# HyperPower.net
KiCad netlist of a schematic drawn in EAGLE
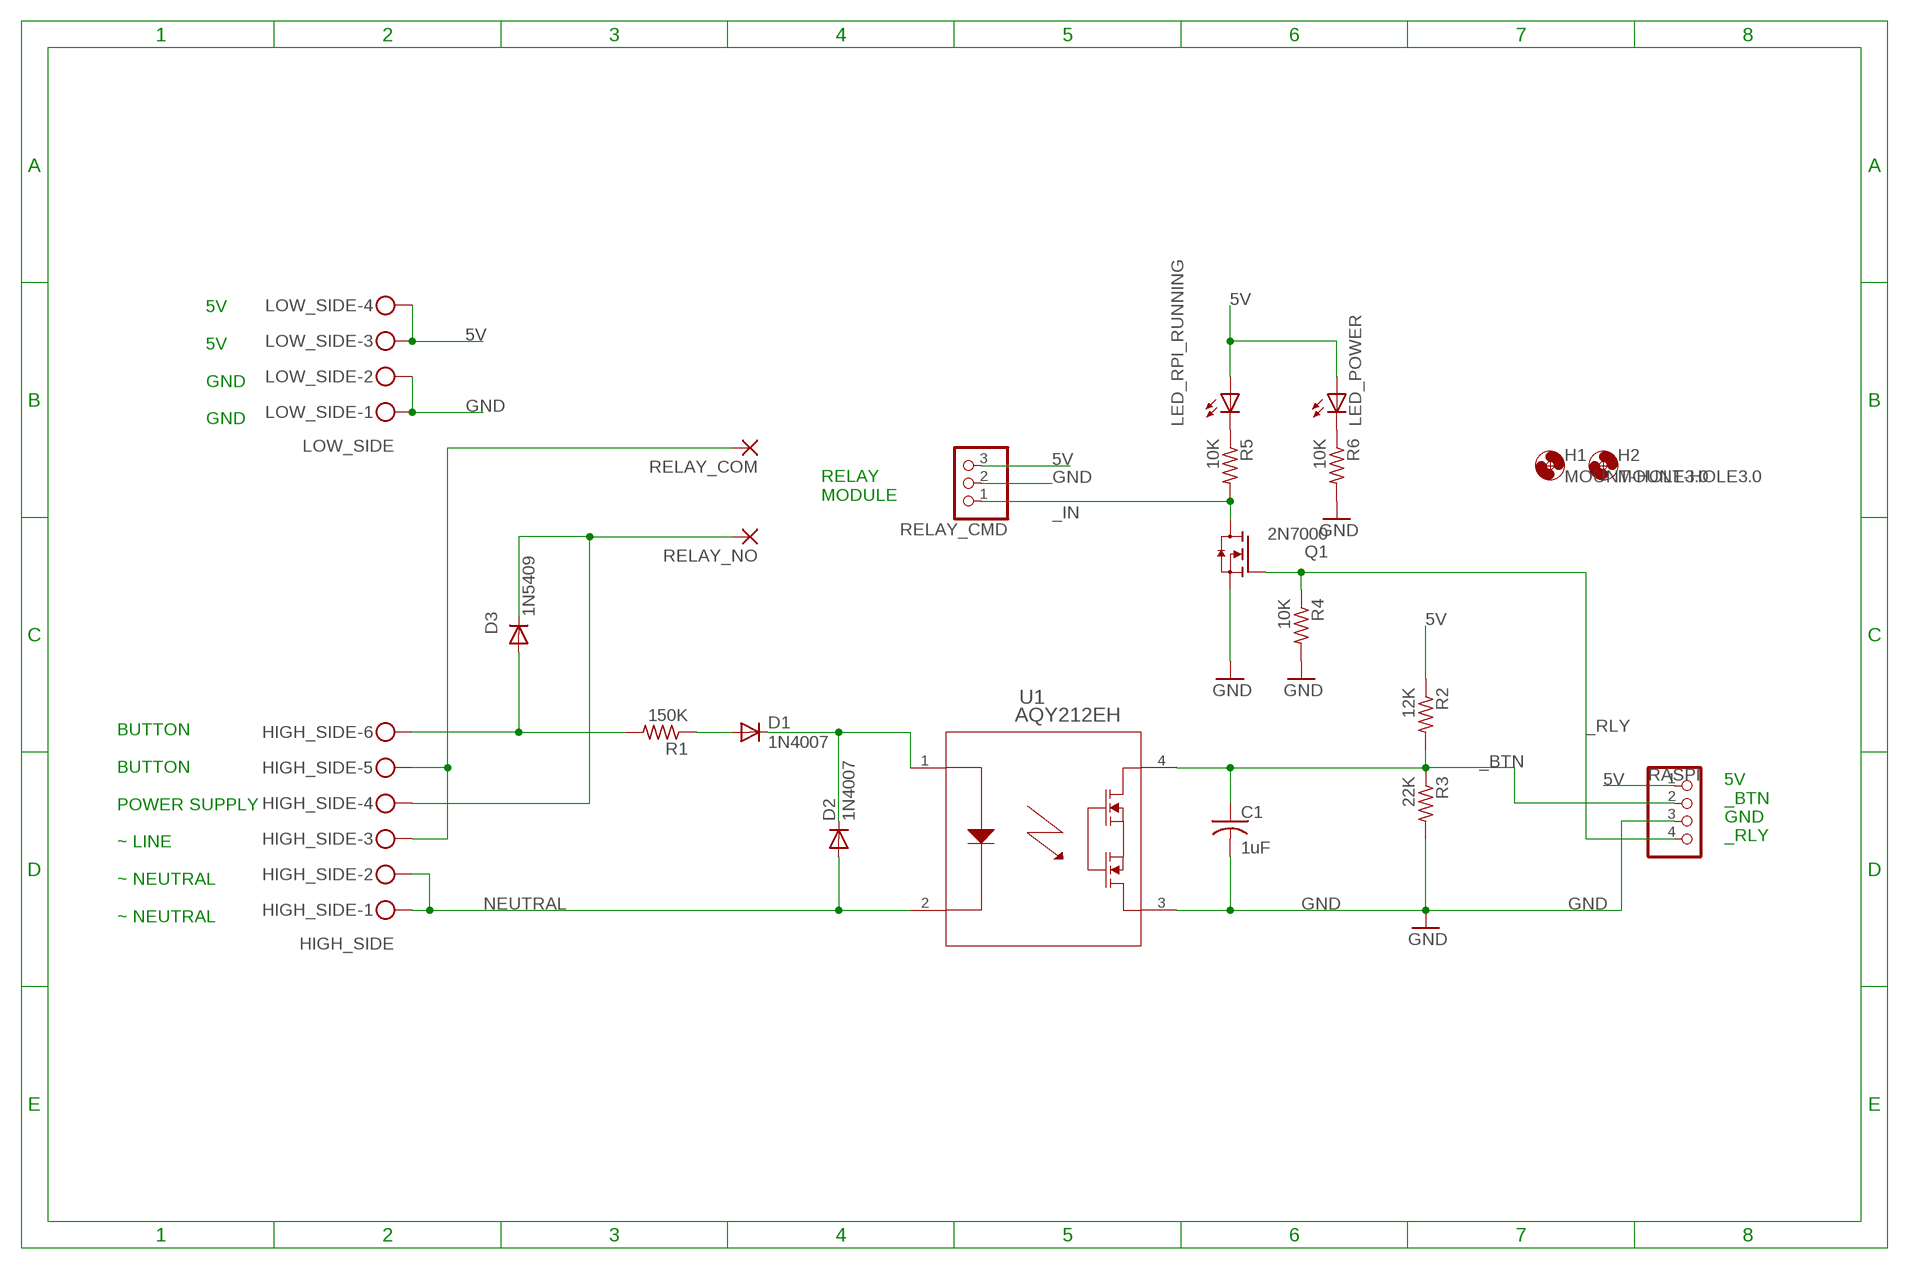
[diagram p0: schematic, sheet 1]

(export (version "E")
  (design (tool "Eeschema 10.0.6"))
  (components
    (comp (ref "C1")
      (value "1uF")
      (footprint "eagle-import:C025-040X050")
      (libsource (lib "eagle-import") (part "C-US025-040X050"))
    )
    (comp (ref "D1")
      (value "1N4007")
      (footprint "eagle-import:DO41-10")
      (libsource (lib "eagle-import") (part "1N4004"))
    )
    (comp (ref "D2")
      (value "1N4007")
      (footprint "eagle-import:DO41-10")
      (libsource (lib "eagle-import") (part "1N4004"))
    )
    (comp (ref "D3")
      (value "1N5409")
      (footprint "eagle-import:DO201-15")
      (libsource (lib "eagle-import") (part "1N5400"))
    )
    (comp (ref "H1")
      (value "MOUNT-HOLE3.0")
      (footprint "eagle-import:3,0")
      (libsource (lib "eagle-import") (part "MOUNT-HOLE3.0"))
    )
    (comp (ref "H2")
      (value "MOUNT-HOLE3.0")
      (footprint "eagle-import:3,0")
      (libsource (lib "eagle-import") (part "MOUNT-HOLE3.0"))
    )
    (comp (ref "HIGH_SIDE")
      (value "HIGH_SIDE")
      (footprint "eagle-import:MKDSN1,5_6-5,08")
      (libsource (lib "eagle-import") (part "MKDSN1,5/6-5,08"))
    )
    (comp (ref "LED_POWER")
      (value "LED_ELD260")
      (footprint "eagle-import:LED_LD260")
      (libsource (lib "eagle-import") (part "LED_ELD260"))
    )
    (comp (ref "LED_RPI_RUNNING")
      (value "LED_ELD260")
      (footprint "eagle-import:LED_LD260")
      (libsource (lib "eagle-import") (part "LED_ELD260"))
    )
    (comp (ref "LOW_SIDE")
      (value "LOW_SIDE")
      (footprint "eagle-import:MKDSN1,5_4-5,08")
      (libsource (lib "eagle-import") (part "MKDSN1,5/4-5,08"))
    )
    (comp (ref "Q1")
      (value "2N7000")
      (footprint "eagle-import:TO92")
      (fields (field (name "MF") "STMicroelectronics"))
      (libsource (lib "eagle-import") (part "2N7000"))
    )
    (comp (ref "R1")
      (value "150K")
      (footprint "eagle-import:0207_10")
      (libsource (lib "eagle-import") (part "R-US_0207/10"))
    )
    (comp (ref "R2")
      (value "12K")
      (footprint "eagle-import:0207_10")
      (libsource (lib "eagle-import") (part "R-US_0207/10"))
    )
    (comp (ref "R3")
      (value "22K")
      (footprint "eagle-import:0207_10")
      (libsource (lib "eagle-import") (part "R-US_0207/10"))
    )
    (comp (ref "R4")
      (value "10K")
      (footprint "eagle-import:0207_10")
      (libsource (lib "eagle-import") (part "R-US_0207/10"))
    )
    (comp (ref "R5")
      (value "10K")
      (footprint "eagle-import:0207_10")
      (libsource (lib "eagle-import") (part "R-US_0207/10"))
    )
    (comp (ref "R6")
      (value "10K")
      (footprint "eagle-import:0207_10")
      (libsource (lib "eagle-import") (part "R-US_0207/10"))
    )
    (comp (ref "RASPI")
      (value "PINHD-1X4")
      (footprint "eagle-import:1X04")
      (libsource (lib "eagle-import") (part "PINHD-1X4"))
    )
    (comp (ref "RELAY_CMD")
      (value "PINHD-1X3")
      (footprint "eagle-import:1X03")
      (libsource (lib "eagle-import") (part "PINHD-1X3"))
    )
    (comp (ref "RELAY_COM")
      (value "3,81/1,4")
      (footprint "eagle-import:3,81_1,4")
      (libsource (lib "eagle-import") (part "3,81/1,4"))
    )
    (comp (ref "RELAY_NO")
      (value "3,81/1,4")
      (footprint "eagle-import:3,81_1,4")
      (libsource (lib "eagle-import") (part "3,81/1,4"))
    )
    (comp (ref "U1")
      (value "AQY212EH")
      (footprint "eagle-import:PAN_AQY21-DIP4_PAN")
      (libsource (lib "eagle-import") (part "AQY212EH"))
    )
  )
  (nets
    (net (code "1") (name "/5V") (class "Default")
      (node (ref "LED_POWER") (pin "A") (pinfunction "A_A") (pintype "passive"))
      (node (ref "LED_RPI_RUNNING") (pin "A") (pinfunction "A_A") (pintype "passive"))
      (node (ref "LOW_SIDE") (pin "3") (pinfunction "KL_3") (pintype "passive"))
      (node (ref "LOW_SIDE") (pin "4") (pinfunction "KL_4") (pintype "passive"))
      (node (ref "R2") (pin "1") (pinfunction "1_1") (pintype "passive"))
      (node (ref "RASPI") (pin "1") (pinfunction "1_1") (pintype "passive"))
      (node (ref "RELAY_CMD") (pin "3") (pinfunction "3_3") (pintype "passive"))
    )
    (net (code "2") (name "/NEUTRAL") (class "Default")
      (node (ref "D2") (pin "A") (pinfunction "A_A") (pintype "passive"))
      (node (ref "HIGH_SIDE") (pin "1") (pinfunction "KL_1") (pintype "passive"))
      (node (ref "HIGH_SIDE") (pin "2") (pinfunction "KL_2") (pintype "passive"))
      (node (ref "U1") (pin "2") (pinfunction "2_2") (pintype "passive"))
    )
    (net (code "3") (name "/_BTN") (class "Default")
      (node (ref "C1") (pin "1") (pinfunction "1_1") (pintype "passive"))
      (node (ref "R2") (pin "2") (pinfunction "2_2") (pintype "passive"))
      (node (ref "R3") (pin "1") (pinfunction "1_1") (pintype "passive"))
      (node (ref "RASPI") (pin "2") (pinfunction "2_2") (pintype "passive"))
      (node (ref "U1") (pin "4") (pinfunction "4_4") (pintype "passive"))
    )
    (net (code "4") (name "/_IN") (class "Default")
      (node (ref "Q1") (pin "3") (pinfunction "D_3") (pintype "passive"))
      (node (ref "R5") (pin "2") (pinfunction "2_2") (pintype "passive"))
      (node (ref "RELAY_CMD") (pin "1") (pinfunction "1_1") (pintype "passive"))
    )
    (net (code "5") (name "/_RLY") (class "Default")
      (node (ref "Q1") (pin "2") (pinfunction "G_2") (pintype "passive"))
      (node (ref "R4") (pin "1") (pinfunction "1_1") (pintype "passive"))
      (node (ref "RASPI") (pin "4") (pinfunction "4_4") (pintype "passive"))
    )
    (net (code "6") (name "GND") (class "Default")
      (node (ref "C1") (pin "2") (pinfunction "2_2") (pintype "passive"))
      (node (ref "LOW_SIDE") (pin "1") (pinfunction "KL_1") (pintype "passive"))
      (node (ref "LOW_SIDE") (pin "2") (pinfunction "KL_2") (pintype "passive"))
      (node (ref "Q1") (pin "1") (pinfunction "S_1") (pintype "passive"))
      (node (ref "R3") (pin "2") (pinfunction "2_2") (pintype "passive"))
      (node (ref "R4") (pin "2") (pinfunction "2_2") (pintype "passive"))
      (node (ref "R6") (pin "2") (pinfunction "2_2") (pintype "passive"))
      (node (ref "RASPI") (pin "3") (pinfunction "3_3") (pintype "passive"))
      (node (ref "RELAY_CMD") (pin "2") (pinfunction "2_2") (pintype "passive"))
      (node (ref "U1") (pin "3") (pinfunction "3_3") (pintype "passive"))
    )
    (net (code "7") (name "Net-(D1-PadA)") (class "Default")
      (node (ref "D1") (pin "A") (pinfunction "A_A") (pintype "passive"))
      (node (ref "R1") (pin "1") (pinfunction "1_1") (pintype "passive"))
    )
    (net (code "8") (name "Net-(D1-PadC)") (class "Default")
      (node (ref "D1") (pin "C") (pinfunction "C_C") (pintype "passive"))
      (node (ref "D2") (pin "C") (pinfunction "C_C") (pintype "passive"))
      (node (ref "U1") (pin "1") (pinfunction "1_1") (pintype "passive"))
    )
    (net (code "9") (name "Net-(HIGH_SIDEC-KL)") (class "Default")
      (node (ref "HIGH_SIDE") (pin "3") (pinfunction "KL_3") (pintype "passive"))
      (node (ref "HIGH_SIDE") (pin "5") (pinfunction "KL_5") (pintype "passive"))
      (node (ref "RELAY_COM") (pin "1") (pinfunction "P_1") (pintype "passive"))
    )
    (net (code "10") (name "Net-(HIGH_SIDED-KL)") (class "Default")
      (node (ref "D3") (pin "C") (pinfunction "C_C") (pintype "passive"))
      (node (ref "HIGH_SIDE") (pin "4") (pinfunction "KL_4") (pintype "passive"))
      (node (ref "RELAY_NO") (pin "1") (pinfunction "P_1") (pintype "passive"))
    )
    (net (code "11") (name "Net-(HIGH_SIDEF-KL)") (class "Default")
      (node (ref "D3") (pin "A") (pinfunction "A_A") (pintype "passive"))
      (node (ref "HIGH_SIDE") (pin "6") (pinfunction "KL_6") (pintype "passive"))
      (node (ref "R1") (pin "2") (pinfunction "2_2") (pintype "passive"))
    )
    (net (code "12") (name "Net-(LED_POWER-C)") (class "Default")
      (node (ref "LED_POWER") (pin "K") (pinfunction "C_K") (pintype "passive"))
      (node (ref "R6") (pin "1") (pinfunction "1_1") (pintype "passive"))
    )
    (net (code "13") (name "Net-(LED_RPI_RUNNING-C)") (class "Default")
      (node (ref "LED_RPI_RUNNING") (pin "K") (pinfunction "C_K") (pintype "passive"))
      (node (ref "R5") (pin "1") (pinfunction "1_1") (pintype "passive"))
    )
  )
)
